# DiveComputer_Flash.net
KiCad netlist of a schematic drawn in EAGLE
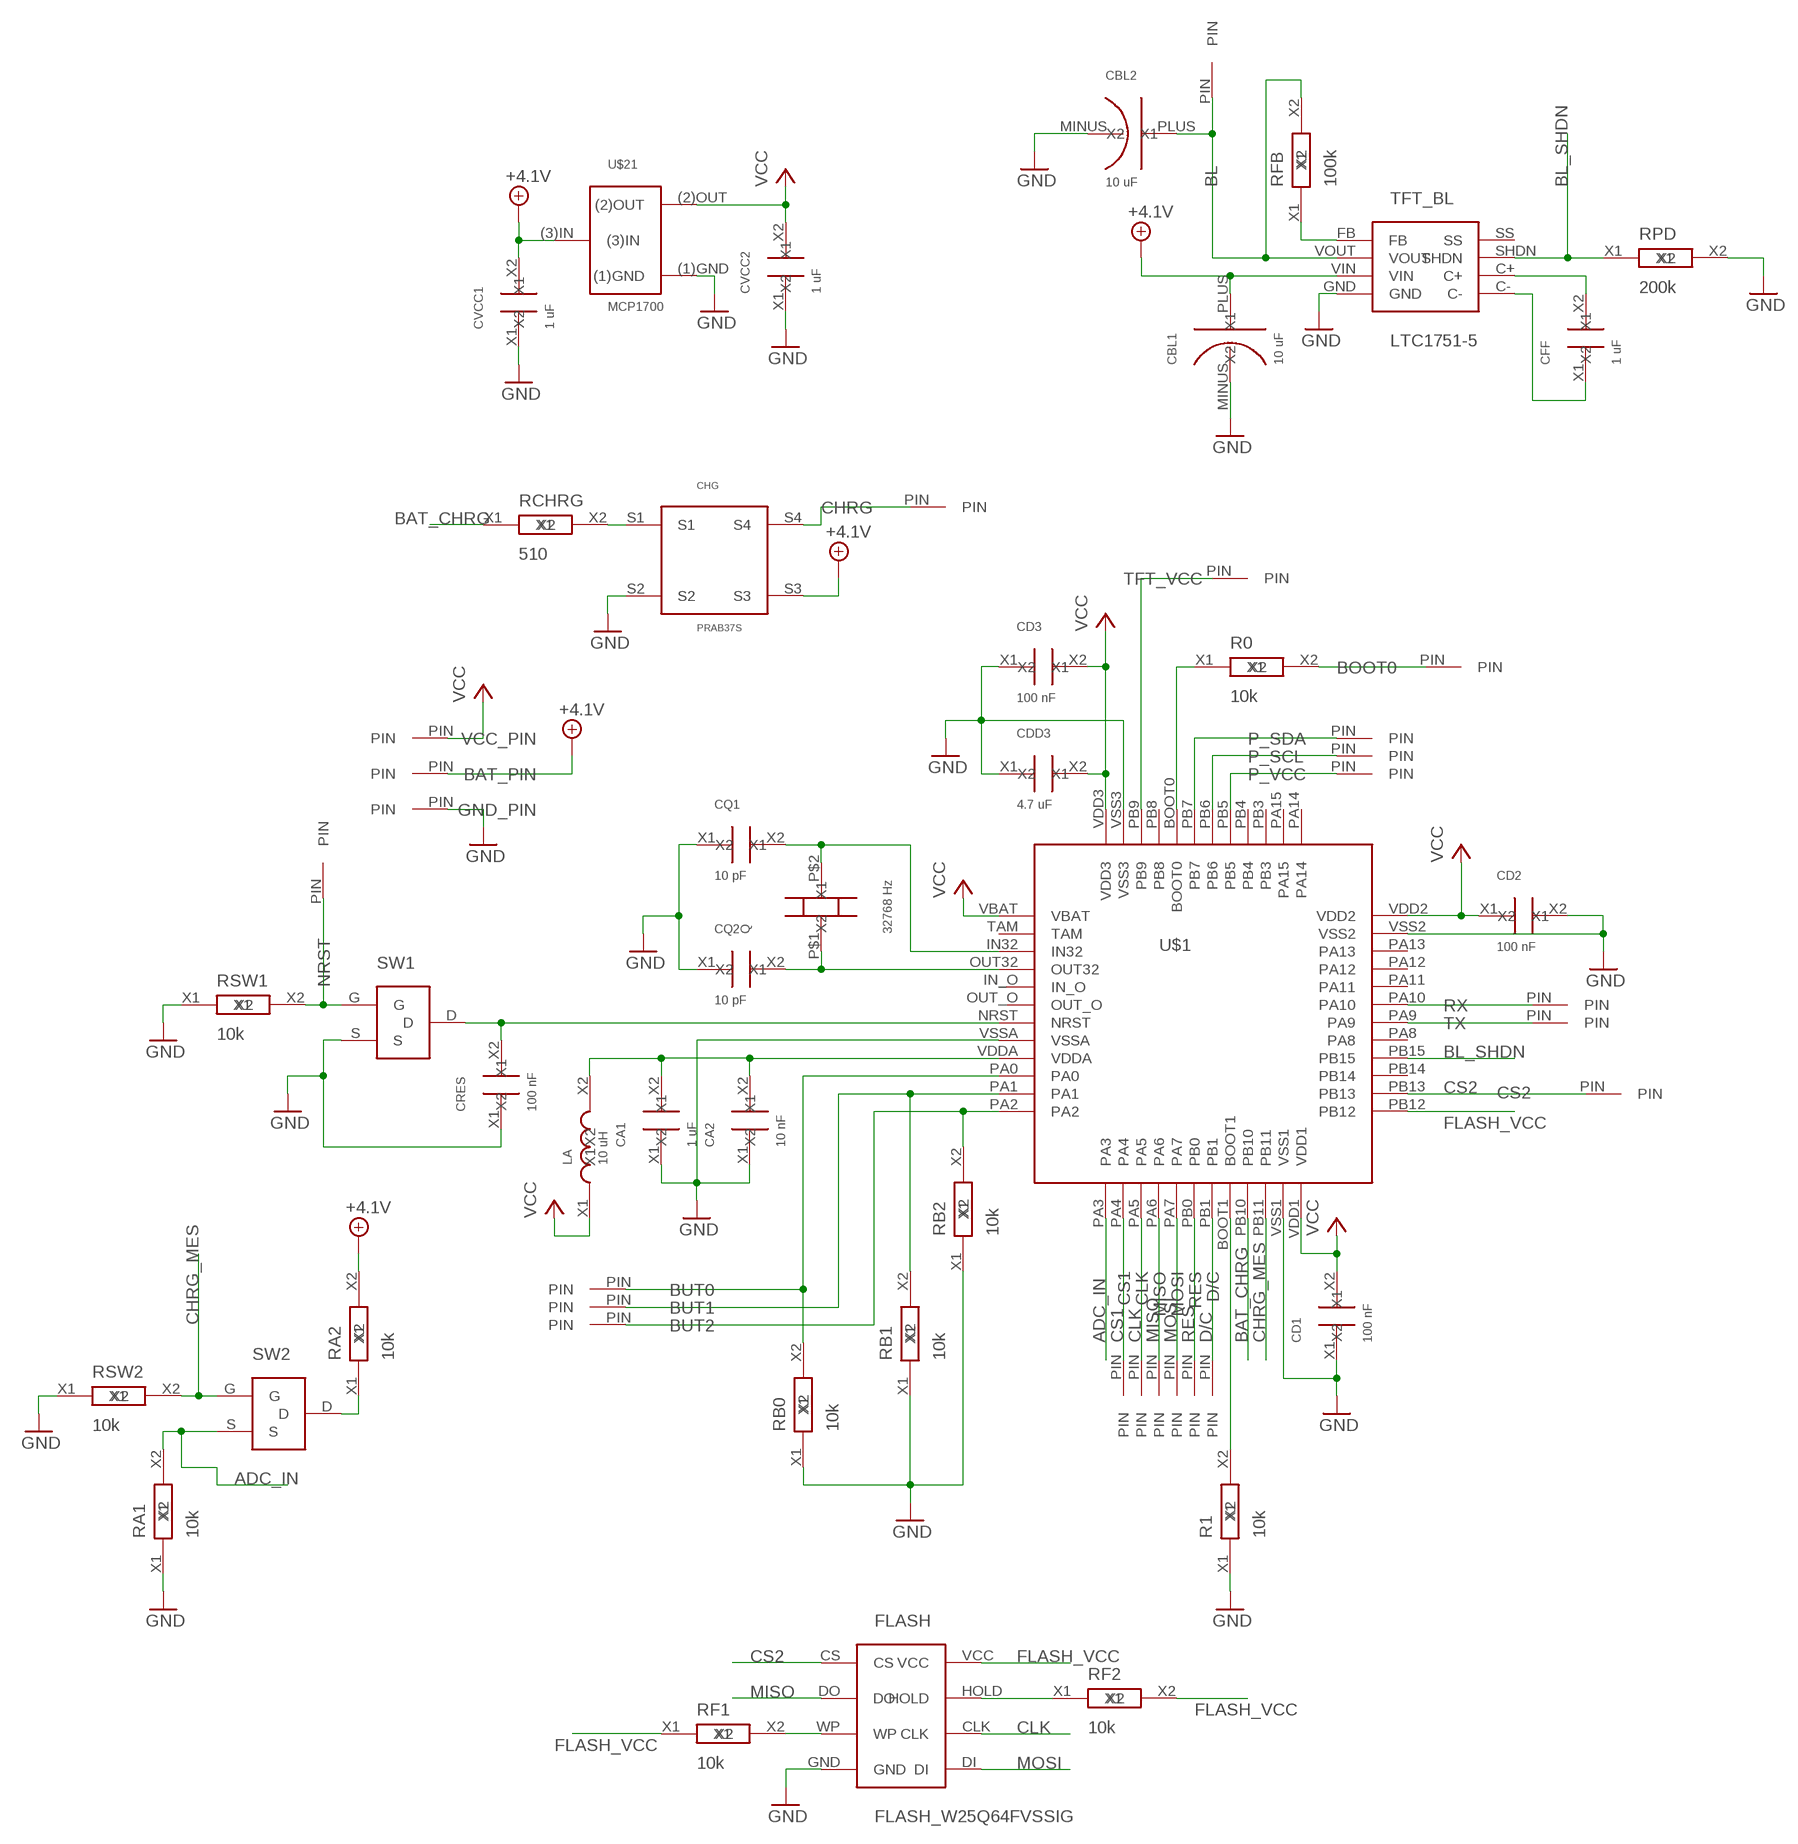
[diagram p0: schematic, sheet 1]

(export (version "E")
  (design (tool "Eeschema 10.0.6"))
  (components
    (comp (ref "BAT_PIN")
      (value "PIN_06")
      (footprint "eagle-import:PIN_06")
      (libsource (lib "eagle-import") (part "PIN_06"))
    )
    (comp (ref "BL")
      (value "PIN_06")
      (footprint "eagle-import:PIN_06")
      (libsource (lib "eagle-import") (part "PIN_06"))
    )
    (comp (ref "BOOT0")
      (value "PIN_06")
      (footprint "eagle-import:PIN_06")
      (libsource (lib "eagle-import") (part "PIN_06"))
    )
    (comp (ref "BUT0")
      (value "PIN_06")
      (footprint "eagle-import:PIN_06")
      (libsource (lib "eagle-import") (part "PIN_06"))
    )
    (comp (ref "BUT1")
      (value "PIN_06")
      (footprint "eagle-import:PIN_06")
      (libsource (lib "eagle-import") (part "PIN_06"))
    )
    (comp (ref "BUT2")
      (value "PIN_06")
      (footprint "eagle-import:PIN_06")
      (libsource (lib "eagle-import") (part "PIN_06"))
    )
    (comp (ref "CA1")
      (value "1 uF")
      (footprint "eagle-import:SMD_2.1X1.25")
      (libsource (lib "eagle-import") (part "C_SMD_2.1X1.25"))
    )
    (comp (ref "CA2")
      (value "10 nF")
      (footprint "eagle-import:SMD_2.1X1.25")
      (libsource (lib "eagle-import") (part "C_SMD_2.1X1.25"))
    )
    (comp (ref "CBL1")
      (value "10 uF")
      (footprint "eagle-import:C_SMD_TA_A")
      (libsource (lib "eagle-import") (part "C_SMD_TA_A"))
    )
    (comp (ref "CBL2")
      (value "10 uF")
      (footprint "eagle-import:C_SMD_TA_A")
      (libsource (lib "eagle-import") (part "C_SMD_TA_A"))
    )
    (comp (ref "CD1")
      (value "100 nF")
      (footprint "eagle-import:SMD_2.1X1.25")
      (libsource (lib "eagle-import") (part "C_SMD_2.1X1.25"))
    )
    (comp (ref "CD2")
      (value "100 nF")
      (footprint "eagle-import:SMD_2.1X1.25")
      (libsource (lib "eagle-import") (part "C_SMD_2.1X1.25"))
    )
    (comp (ref "CD3")
      (value "100 nF")
      (footprint "eagle-import:SMD_2.1X1.25")
      (libsource (lib "eagle-import") (part "C_SMD_2.1X1.25"))
    )
    (comp (ref "CDD3")
      (value "4.7 uF")
      (footprint "eagle-import:SMD_2.1X1.25")
      (libsource (lib "eagle-import") (part "C_SMD_2.1X1.25"))
    )
    (comp (ref "CFF")
      (value "1 uF")
      (footprint "eagle-import:SMD_2.1X1.25")
      (libsource (lib "eagle-import") (part "C_SMD_2.1X1.25"))
    )
    (comp (ref "CHG")
      (value "PRAB37S")
      (footprint "eagle-import:PRAB37S")
      (libsource (lib "eagle-import") (part "PRAB37S"))
    )
    (comp (ref "CHRG")
      (value "PIN_06")
      (footprint "eagle-import:PIN_06")
      (libsource (lib "eagle-import") (part "PIN_06"))
    )
    (comp (ref "CLK")
      (value "PIN_06")
      (footprint "eagle-import:PIN_06")
      (libsource (lib "eagle-import") (part "PIN_06"))
    )
    (comp (ref "CQ1")
      (value "10 pF")
      (footprint "eagle-import:SMD_2.1X1.25")
      (libsource (lib "eagle-import") (part "C_SMD_2.1X1.25"))
    )
    (comp (ref "CQ2")
      (value "10 pF")
      (footprint "eagle-import:SMD_2.1X1.25")
      (libsource (lib "eagle-import") (part "C_SMD_2.1X1.25"))
    )
    (comp (ref "CRES")
      (value "100 nF")
      (footprint "eagle-import:SMD_2.1X1.25")
      (libsource (lib "eagle-import") (part "C_SMD_2.1X1.25"))
    )
    (comp (ref "CS1")
      (value "PIN_06")
      (footprint "eagle-import:PIN_06")
      (libsource (lib "eagle-import") (part "PIN_06"))
    )
    (comp (ref "CS2")
      (value "PIN_06")
      (footprint "eagle-import:PIN_06")
      (libsource (lib "eagle-import") (part "PIN_06"))
    )
    (comp (ref "CVCC1")
      (value "1 uF")
      (footprint "eagle-import:SMD_2.1X1.25")
      (libsource (lib "eagle-import") (part "C_SMD_2.1X1.25"))
    )
    (comp (ref "CVCC2")
      (value "1 uF")
      (footprint "eagle-import:SMD_2.1X1.25")
      (libsource (lib "eagle-import") (part "C_SMD_2.1X1.25"))
    )
    (comp (ref "D/C")
      (value "PIN_06")
      (footprint "eagle-import:PIN_06")
      (libsource (lib "eagle-import") (part "PIN_06"))
    )
    (comp (ref "FLASH")
      (value "FLASH_W25Q64FVSSIG")
      (footprint "eagle-import:FLASH_W25Q64FVSSIG")
      (libsource (lib "eagle-import") (part "FLASH_W25Q64FVSSIG"))
    )
    (comp (ref "GND_PIN")
      (value "PIN_06")
      (footprint "eagle-import:PIN_06")
      (libsource (lib "eagle-import") (part "PIN_06"))
    )
    (comp (ref "LA")
      (value "10 uH")
      (footprint "eagle-import:SMD_2.1X1.25")
      (libsource (lib "eagle-import") (part "L_SMD_2.1X1.25"))
    )
    (comp (ref "MISO")
      (value "PIN_06")
      (footprint "eagle-import:PIN_06")
      (libsource (lib "eagle-import") (part "PIN_06"))
    )
    (comp (ref "MOSI")
      (value "PIN_06")
      (footprint "eagle-import:PIN_06")
      (libsource (lib "eagle-import") (part "PIN_06"))
    )
    (comp (ref "NRST")
      (value "PIN_06")
      (footprint "eagle-import:PIN_06")
      (libsource (lib "eagle-import") (part "PIN_06"))
    )
    (comp (ref "P_SCL")
      (value "PIN_06")
      (footprint "eagle-import:PIN_06")
      (libsource (lib "eagle-import") (part "PIN_06"))
    )
    (comp (ref "P_SDA")
      (value "PIN_06")
      (footprint "eagle-import:PIN_06")
      (libsource (lib "eagle-import") (part "PIN_06"))
    )
    (comp (ref "P_VCC")
      (value "PIN_06")
      (footprint "eagle-import:PIN_06")
      (libsource (lib "eagle-import") (part "PIN_06"))
    )
    (comp (ref "Q")
      (value "32768 Hz")
      (footprint "eagle-import:QUARTZ_CYL")
      (libsource (lib "eagle-import") (part "QUARTZ_CYL"))
    )
    (comp (ref "R0")
      (value "10k")
      (footprint "eagle-import:SMD_2.1X1.25")
      (libsource (lib "eagle-import") (part "R_SMD_2.1X1.25"))
    )
    (comp (ref "R1")
      (value "10k")
      (footprint "eagle-import:SMD_2.1X1.25")
      (libsource (lib "eagle-import") (part "R_SMD_2.1X1.25"))
    )
    (comp (ref "RA1")
      (value "10k")
      (footprint "eagle-import:SMD_2.1X1.25")
      (libsource (lib "eagle-import") (part "R_SMD_2.1X1.25"))
    )
    (comp (ref "RA2")
      (value "10k")
      (footprint "eagle-import:SMD_2.1X1.25")
      (libsource (lib "eagle-import") (part "R_SMD_2.1X1.25"))
    )
    (comp (ref "RB0")
      (value "10k")
      (footprint "eagle-import:SMD_2.1X1.25")
      (libsource (lib "eagle-import") (part "R_SMD_2.1X1.25"))
    )
    (comp (ref "RB1")
      (value "10k")
      (footprint "eagle-import:SMD_2.1X1.25")
      (libsource (lib "eagle-import") (part "R_SMD_2.1X1.25"))
    )
    (comp (ref "RB2")
      (value "10k")
      (footprint "eagle-import:SMD_2.1X1.25")
      (libsource (lib "eagle-import") (part "R_SMD_2.1X1.25"))
    )
    (comp (ref "RCHRG")
      (value "510")
      (footprint "eagle-import:SMD_2.1X1.25")
      (libsource (lib "eagle-import") (part "R_SMD_2.1X1.25"))
    )
    (comp (ref "RES")
      (value "PIN_06")
      (footprint "eagle-import:PIN_06")
      (libsource (lib "eagle-import") (part "PIN_06"))
    )
    (comp (ref "RF1")
      (value "10k")
      (footprint "eagle-import:SMD_2.1X1.25")
      (libsource (lib "eagle-import") (part "R_SMD_2.1X1.25"))
    )
    (comp (ref "RF2")
      (value "10k")
      (footprint "eagle-import:SMD_2.1X1.25")
      (libsource (lib "eagle-import") (part "R_SMD_2.1X1.25"))
    )
    (comp (ref "RFB")
      (value "100k")
      (footprint "eagle-import:SMD_2.1X1.25")
      (libsource (lib "eagle-import") (part "R_SMD_2.1X1.25"))
    )
    (comp (ref "RPD")
      (value "200k")
      (footprint "eagle-import:SMD_2.1X1.25")
      (libsource (lib "eagle-import") (part "R_SMD_2.1X1.25"))
    )
    (comp (ref "RSW1")
      (value "10k")
      (footprint "eagle-import:SMD_2.1X1.25")
      (libsource (lib "eagle-import") (part "R_SMD_2.1X1.25"))
    )
    (comp (ref "RSW2")
      (value "10k")
      (footprint "eagle-import:SMD_2.1X1.25")
      (libsource (lib "eagle-import") (part "R_SMD_2.1X1.25"))
    )
    (comp (ref "RX")
      (value "PIN_06")
      (footprint "eagle-import:PIN_06")
      (libsource (lib "eagle-import") (part "PIN_06"))
    )
    (comp (ref "SW1")
      (value "IRFML8244TRPBF")
      (footprint "eagle-import:IRFML8244TRPBF")
      (libsource (lib "eagle-import") (part "IRFML8244TRPBF"))
    )
    (comp (ref "SW2")
      (value "IRFML8244TRPBF")
      (footprint "eagle-import:IRFML8244TRPBF")
      (libsource (lib "eagle-import") (part "IRFML8244TRPBF"))
    )
    (comp (ref "TFT_BL")
      (value "LTC1751-5")
      (footprint "eagle-import:LTC1751-5")
      (libsource (lib "eagle-import") (part "LTC1751-5"))
    )
    (comp (ref "TFT_VCC")
      (value "PIN_06")
      (footprint "eagle-import:PIN_06")
      (libsource (lib "eagle-import") (part "PIN_06"))
    )
    (comp (ref "TX")
      (value "PIN_06")
      (footprint "eagle-import:PIN_06")
      (libsource (lib "eagle-import") (part "PIN_06"))
    )
    (comp (ref "U$1")
      (value "STM32F103CBT6")
      (footprint "eagle-import:STM32F103CBT6")
      (libsource (lib "eagle-import") (part "STM32F103CBT6"))
    )
    (comp (ref "U$21")
      (value "MCP1700")
      (footprint "eagle-import:MCP1700")
      (libsource (lib "eagle-import") (part "MCP1700"))
    )
    (comp (ref "VCC_PIN")
      (value "PIN_06")
      (footprint "eagle-import:PIN_06")
      (libsource (lib "eagle-import") (part "PIN_06"))
    )
  )
  (nets
    (net (code "1") (name "+4.1V") (class "Default")
      (node (ref "BAT_PIN") (pin "PIN") (pinfunction "PIN_PIN") (pintype "bidirectional"))
      (node (ref "CBL1") (pin "PLUS") (pinfunction "X2_PLUS") (pintype "bidirectional"))
      (node (ref "CHG") (pin "S3") (pinfunction "S3_S3") (pintype "bidirectional"))
      (node (ref "CVCC1") (pin "X2") (pinfunction "X2_X2") (pintype "bidirectional"))
      (node (ref "RA2") (pin "X2") (pinfunction "X2_X2") (pintype "bidirectional"))
      (node (ref "TFT_BL") (pin "VIN") (pinfunction "VIN_VIN") (pintype "bidirectional"))
      (node (ref "U$21") (pin "(3)IN") (pinfunction "(3)IN_(3)IN") (pintype "bidirectional"))
    )
    (net (code "2") (name "/ADC_IN") (class "Default")
      (node (ref "RA1") (pin "X2") (pinfunction "X2_X2") (pintype "bidirectional"))
      (node (ref "SW2") (pin "S") (pinfunction "S_S") (pintype "bidirectional"))
      (node (ref "U$1") (pin "PA3") (pinfunction "PA3_PA3") (pintype "bidirectional"))
    )
    (net (code "3") (name "/BAT_CHRG") (class "Default")
      (node (ref "RCHRG") (pin "X1") (pinfunction "X1_X1") (pintype "bidirectional"))
      (node (ref "U$1") (pin "PB10") (pinfunction "PB10_PB10") (pintype "bidirectional"))
    )
    (net (code "4") (name "/BL_SHDN") (class "Default")
      (node (ref "RPD") (pin "X1") (pinfunction "X1_X1") (pintype "bidirectional"))
      (node (ref "TFT_BL") (pin "SHDN") (pinfunction "SHDN_SHDN") (pintype "bidirectional"))
      (node (ref "U$1") (pin "PB15") (pinfunction "PB15_PB15") (pintype "bidirectional"))
    )
    (net (code "5") (name "/CHRG_MES") (class "Default")
      (node (ref "RSW2") (pin "X2") (pinfunction "X2_X2") (pintype "bidirectional"))
      (node (ref "SW2") (pin "G") (pinfunction "G_G") (pintype "bidirectional"))
      (node (ref "U$1") (pin "PB11") (pinfunction "PB11_PB11") (pintype "bidirectional"))
    )
    (net (code "6") (name "/CLK") (class "Default")
      (node (ref "CLK") (pin "PIN") (pinfunction "PIN_PIN") (pintype "bidirectional"))
      (node (ref "FLASH") (pin "CLK") (pinfunction "CLK_CLK") (pintype "bidirectional"))
      (node (ref "U$1") (pin "PA5") (pinfunction "PA5_PA5") (pintype "bidirectional"))
    )
    (net (code "7") (name "/CS1") (class "Default")
      (node (ref "CS1") (pin "PIN") (pinfunction "PIN_PIN") (pintype "bidirectional"))
      (node (ref "U$1") (pin "PA4") (pinfunction "PA4_PA4") (pintype "bidirectional"))
    )
    (net (code "8") (name "/CS2") (class "Default")
      (node (ref "CS2") (pin "PIN") (pinfunction "PIN_PIN") (pintype "bidirectional"))
      (node (ref "FLASH") (pin "CS") (pinfunction "CS_CS") (pintype "bidirectional"))
      (node (ref "U$1") (pin "PB13") (pinfunction "PB13_PB13") (pintype "bidirectional"))
    )
    (net (code "9") (name "/D{slash}C") (class "Default")
      (node (ref "D/C") (pin "PIN") (pinfunction "PIN_PIN") (pintype "bidirectional"))
      (node (ref "U$1") (pin "PB1") (pinfunction "PB1_PB1") (pintype "bidirectional"))
    )
    (net (code "10") (name "/FLASH_VCC") (class "Default")
      (node (ref "FLASH") (pin "VCC") (pinfunction "VCC_VCC") (pintype "bidirectional"))
      (node (ref "RF1") (pin "X1") (pinfunction "X1_X1") (pintype "bidirectional"))
      (node (ref "RF2") (pin "X2") (pinfunction "X2_X2") (pintype "bidirectional"))
      (node (ref "U$1") (pin "PB12") (pinfunction "PB12_PB12") (pintype "bidirectional"))
    )
    (net (code "11") (name "/MISO") (class "Default")
      (node (ref "FLASH") (pin "DO") (pinfunction "DO_DO") (pintype "bidirectional"))
      (node (ref "MISO") (pin "PIN") (pinfunction "PIN_PIN") (pintype "bidirectional"))
      (node (ref "U$1") (pin "PA6") (pinfunction "PA6_PA6") (pintype "bidirectional"))
    )
    (net (code "12") (name "/MOSI") (class "Default")
      (node (ref "FLASH") (pin "DI") (pinfunction "DI_DI") (pintype "bidirectional"))
      (node (ref "MOSI") (pin "PIN") (pinfunction "PIN_PIN") (pintype "bidirectional"))
      (node (ref "U$1") (pin "PA7") (pinfunction "PA7_PA7") (pintype "bidirectional"))
    )
    (net (code "13") (name "/RES") (class "Default")
      (node (ref "RES") (pin "PIN") (pinfunction "PIN_PIN") (pintype "bidirectional"))
      (node (ref "U$1") (pin "PB0") (pinfunction "PB0_PB0") (pintype "bidirectional"))
    )
    (net (code "14") (name "GND") (class "Default")
      (node (ref "CA1") (pin "X1") (pinfunction "X1_X1") (pintype "bidirectional"))
      (node (ref "CA2") (pin "X1") (pinfunction "X1_X1") (pintype "bidirectional"))
      (node (ref "CBL1") (pin "MINUS") (pinfunction "X1_MINUS") (pintype "bidirectional"))
      (node (ref "CBL2") (pin "MINUS") (pinfunction "X1_MINUS") (pintype "bidirectional"))
      (node (ref "CD1") (pin "X1") (pinfunction "X1_X1") (pintype "bidirectional"))
      (node (ref "CD2") (pin "X2") (pinfunction "X2_X2") (pintype "bidirectional"))
      (node (ref "CD3") (pin "X1") (pinfunction "X1_X1") (pintype "bidirectional"))
      (node (ref "CDD3") (pin "X1") (pinfunction "X1_X1") (pintype "bidirectional"))
      (node (ref "CHG") (pin "S2") (pinfunction "S2_S2") (pintype "bidirectional"))
      (node (ref "CQ1") (pin "X1") (pinfunction "X1_X1") (pintype "bidirectional"))
      (node (ref "CQ2") (pin "X1") (pinfunction "X1_X1") (pintype "bidirectional"))
      (node (ref "CRES") (pin "X1") (pinfunction "X1_X1") (pintype "bidirectional"))
      (node (ref "CVCC1") (pin "X1") (pinfunction "X1_X1") (pintype "bidirectional"))
      (node (ref "CVCC2") (pin "X1") (pinfunction "X1_X1") (pintype "bidirectional"))
      (node (ref "FLASH") (pin "GND") (pinfunction "GND_GND") (pintype "bidirectional"))
      (node (ref "GND_PIN") (pin "PIN") (pinfunction "PIN_PIN") (pintype "bidirectional"))
      (node (ref "R1") (pin "X1") (pinfunction "X1_X1") (pintype "bidirectional"))
      (node (ref "RA1") (pin "X1") (pinfunction "X1_X1") (pintype "bidirectional"))
      (node (ref "RB0") (pin "X1") (pinfunction "X1_X1") (pintype "bidirectional"))
      (node (ref "RB1") (pin "X1") (pinfunction "X1_X1") (pintype "bidirectional"))
      (node (ref "RB2") (pin "X1") (pinfunction "X1_X1") (pintype "bidirectional"))
      (node (ref "RPD") (pin "X2") (pinfunction "X2_X2") (pintype "bidirectional"))
      (node (ref "RSW1") (pin "X1") (pinfunction "X1_X1") (pintype "bidirectional"))
      (node (ref "RSW2") (pin "X1") (pinfunction "X1_X1") (pintype "bidirectional"))
      (node (ref "SW1") (pin "S") (pinfunction "S_S") (pintype "bidirectional"))
      (node (ref "TFT_BL") (pin "GND") (pinfunction "GND_GND") (pintype "bidirectional"))
      (node (ref "U$1") (pin "VSS1") (pinfunction "VSS1_VSS1") (pintype "bidirectional"))
      (node (ref "U$1") (pin "VSS2") (pinfunction "VSS2_VSS2") (pintype "bidirectional"))
      (node (ref "U$1") (pin "VSS3") (pinfunction "VSS3_VSS3") (pintype "bidirectional"))
      (node (ref "U$1") (pin "VSSA") (pinfunction "VSSA_VSSA") (pintype "bidirectional"))
      (node (ref "U$21") (pin "(1)GND") (pinfunction "(1)GND_(1)GND") (pintype "bidirectional"))
    )
    (net (code "15") (name "Net-(BOOT0-PadPIN)") (class "Default")
      (node (ref "BOOT0") (pin "PIN") (pinfunction "PIN_PIN") (pintype "bidirectional"))
      (node (ref "R0") (pin "X2") (pinfunction "X2_X2") (pintype "bidirectional"))
    )
    (net (code "16") (name "Net-(BUT0-PadPIN)") (class "Default")
      (node (ref "BUT0") (pin "PIN") (pinfunction "PIN_PIN") (pintype "bidirectional"))
      (node (ref "RB0") (pin "X2") (pinfunction "X2_X2") (pintype "bidirectional"))
      (node (ref "U$1") (pin "PA0") (pinfunction "PA0_PA0") (pintype "bidirectional"))
    )
    (net (code "17") (name "Net-(BUT1-PadPIN)") (class "Default")
      (node (ref "BUT1") (pin "PIN") (pinfunction "PIN_PIN") (pintype "bidirectional"))
      (node (ref "RB1") (pin "X2") (pinfunction "X2_X2") (pintype "bidirectional"))
      (node (ref "U$1") (pin "PA1") (pinfunction "PA1_PA1") (pintype "bidirectional"))
    )
    (net (code "18") (name "Net-(BUT2-PadPIN)") (class "Default")
      (node (ref "BUT2") (pin "PIN") (pinfunction "PIN_PIN") (pintype "bidirectional"))
      (node (ref "RB2") (pin "X2") (pinfunction "X2_X2") (pintype "bidirectional"))
      (node (ref "U$1") (pin "PA2") (pinfunction "PA2_PA2") (pintype "bidirectional"))
    )
    (net (code "19") (name "Net-(CA1-PadX2)") (class "Default")
      (node (ref "CA1") (pin "X2") (pinfunction "X2_X2") (pintype "bidirectional"))
      (node (ref "CA2") (pin "X2") (pinfunction "X2_X2") (pintype "bidirectional"))
      (node (ref "LA") (pin "X2") (pinfunction "X2_X2") (pintype "bidirectional"))
      (node (ref "U$1") (pin "VDDA") (pinfunction "VDDA_VDDA") (pintype "bidirectional"))
    )
    (net (code "20") (name "Net-(CBL2-X2)") (class "Default")
      (node (ref "BL") (pin "PIN") (pinfunction "PIN_PIN") (pintype "bidirectional"))
      (node (ref "CBL2") (pin "PLUS") (pinfunction "X2_PLUS") (pintype "bidirectional"))
      (node (ref "RFB") (pin "X2") (pinfunction "X2_X2") (pintype "bidirectional"))
      (node (ref "TFT_BL") (pin "VOUT") (pinfunction "VOUT_VOUT") (pintype "bidirectional"))
    )
    (net (code "21") (name "Net-(CFF-PadX1)") (class "Default")
      (node (ref "CFF") (pin "X1") (pinfunction "X1_X1") (pintype "bidirectional"))
      (node (ref "TFT_BL") (pin "C-") (pinfunction "C-_C-") (pintype "bidirectional"))
    )
    (net (code "22") (name "Net-(CFF-PadX2)") (class "Default")
      (node (ref "CFF") (pin "X2") (pinfunction "X2_X2") (pintype "bidirectional"))
      (node (ref "TFT_BL") (pin "C+") (pinfunction "C+_C+") (pintype "bidirectional"))
    )
    (net (code "23") (name "Net-(CHG-PadS1)") (class "Default")
      (node (ref "CHG") (pin "S1") (pinfunction "S1_S1") (pintype "bidirectional"))
      (node (ref "RCHRG") (pin "X2") (pinfunction "X2_X2") (pintype "bidirectional"))
    )
    (net (code "24") (name "Net-(CHG-PadS4)") (class "Default")
      (node (ref "CHG") (pin "S4") (pinfunction "S4_S4") (pintype "bidirectional"))
      (node (ref "CHRG") (pin "PIN") (pinfunction "PIN_PIN") (pintype "bidirectional"))
    )
    (net (code "25") (name "Net-(CRES-PadX2)") (class "Default")
      (node (ref "CRES") (pin "X2") (pinfunction "X2_X2") (pintype "bidirectional"))
      (node (ref "SW1") (pin "D") (pinfunction "D_D") (pintype "bidirectional"))
      (node (ref "U$1") (pin "NRST") (pinfunction "NRST_NRST") (pintype "bidirectional"))
    )
    (net (code "26") (name "Net-(FLASH-PadHOLD)") (class "Default")
      (node (ref "FLASH") (pin "HOLD") (pinfunction "HOLD_HOLD") (pintype "bidirectional"))
      (node (ref "RF2") (pin "X1") (pinfunction "X1_X1") (pintype "bidirectional"))
    )
    (net (code "27") (name "Net-(FLASH-PadWP)") (class "Default")
      (node (ref "FLASH") (pin "WP") (pinfunction "WP_WP") (pintype "bidirectional"))
      (node (ref "RF1") (pin "X2") (pinfunction "X2_X2") (pintype "bidirectional"))
    )
    (net (code "28") (name "Net-(NRST-PadPIN)") (class "Default")
      (node (ref "NRST") (pin "PIN") (pinfunction "PIN_PIN") (pintype "bidirectional"))
      (node (ref "RSW1") (pin "X2") (pinfunction "X2_X2") (pintype "bidirectional"))
      (node (ref "SW1") (pin "G") (pinfunction "G_G") (pintype "bidirectional"))
    )
    (net (code "29") (name "Net-(P_SCL-PadPIN)") (class "Default")
      (node (ref "P_SCL") (pin "PIN") (pinfunction "PIN_PIN") (pintype "bidirectional"))
      (node (ref "U$1") (pin "PB6") (pinfunction "PB6_PB6") (pintype "bidirectional"))
    )
    (net (code "30") (name "Net-(P_SDA-PadPIN)") (class "Default")
      (node (ref "P_SDA") (pin "PIN") (pinfunction "PIN_PIN") (pintype "bidirectional"))
      (node (ref "U$1") (pin "PB7") (pinfunction "PB7_PB7") (pintype "bidirectional"))
    )
    (net (code "31") (name "Net-(P_VCC-PadPIN)") (class "Default")
      (node (ref "P_VCC") (pin "PIN") (pinfunction "PIN_PIN") (pintype "bidirectional"))
      (node (ref "U$1") (pin "PB5") (pinfunction "PB5_PB5") (pintype "bidirectional"))
    )
    (net (code "32") (name "Net-(Q-X1)") (class "Default")
      (node (ref "CQ2") (pin "X2") (pinfunction "X2_X2") (pintype "bidirectional"))
      (node (ref "Q") (pin "P$1") (pinfunction "X1_P$1") (pintype "bidirectional"))
      (node (ref "U$1") (pin "OUT32") (pinfunction "OUT32_OUT32") (pintype "bidirectional"))
    )
    (net (code "33") (name "Net-(Q-X2)") (class "Default")
      (node (ref "CQ1") (pin "X2") (pinfunction "X2_X2") (pintype "bidirectional"))
      (node (ref "Q") (pin "P$2") (pinfunction "X2_P$2") (pintype "bidirectional"))
      (node (ref "U$1") (pin "IN32") (pinfunction "IN32_IN32") (pintype "bidirectional"))
    )
    (net (code "34") (name "Net-(R0-PadX1)") (class "Default")
      (node (ref "R0") (pin "X1") (pinfunction "X1_X1") (pintype "bidirectional"))
      (node (ref "U$1") (pin "BOOT0") (pinfunction "BOOT0_BOOT0") (pintype "bidirectional"))
    )
    (net (code "35") (name "Net-(R1-PadX2)") (class "Default")
      (node (ref "R1") (pin "X2") (pinfunction "X2_X2") (pintype "bidirectional"))
      (node (ref "U$1") (pin "BOOT1") (pinfunction "BOOT1_BOOT1") (pintype "bidirectional"))
    )
    (net (code "36") (name "Net-(RA2-PadX1)") (class "Default")
      (node (ref "RA2") (pin "X1") (pinfunction "X1_X1") (pintype "bidirectional"))
      (node (ref "SW2") (pin "D") (pinfunction "D_D") (pintype "bidirectional"))
    )
    (net (code "37") (name "Net-(RFB-PadX1)") (class "Default")
      (node (ref "RFB") (pin "X1") (pinfunction "X1_X1") (pintype "bidirectional"))
      (node (ref "TFT_BL") (pin "FB") (pinfunction "FB_FB") (pintype "bidirectional"))
    )
    (net (code "38") (name "Net-(RX-PadPIN)") (class "Default")
      (node (ref "RX") (pin "PIN") (pinfunction "PIN_PIN") (pintype "bidirectional"))
      (node (ref "U$1") (pin "PA10") (pinfunction "PA10_PA10") (pintype "bidirectional"))
    )
    (net (code "39") (name "Net-(TFT_VCC-PadPIN)") (class "Default")
      (node (ref "TFT_VCC") (pin "PIN") (pinfunction "PIN_PIN") (pintype "bidirectional"))
      (node (ref "U$1") (pin "PB9") (pinfunction "PB9_PB9") (pintype "bidirectional"))
    )
    (net (code "40") (name "Net-(TX-PadPIN)") (class "Default")
      (node (ref "TX") (pin "PIN") (pinfunction "PIN_PIN") (pintype "bidirectional"))
      (node (ref "U$1") (pin "PA9") (pinfunction "PA9_PA9") (pintype "bidirectional"))
    )
    (net (code "41") (name "VCC") (class "Default")
      (node (ref "CD1") (pin "X2") (pinfunction "X2_X2") (pintype "bidirectional"))
      (node (ref "CD2") (pin "X1") (pinfunction "X1_X1") (pintype "bidirectional"))
      (node (ref "CD3") (pin "X2") (pinfunction "X2_X2") (pintype "bidirectional"))
      (node (ref "CDD3") (pin "X2") (pinfunction "X2_X2") (pintype "bidirectional"))
      (node (ref "CVCC2") (pin "X2") (pinfunction "X2_X2") (pintype "bidirectional"))
      (node (ref "LA") (pin "X1") (pinfunction "X1_X1") (pintype "bidirectional"))
      (node (ref "U$1") (pin "VBAT") (pinfunction "VBAT_VBAT") (pintype "bidirectional"))
      (node (ref "U$1") (pin "VDD1") (pinfunction "VDD1_VDD1") (pintype "bidirectional"))
      (node (ref "U$1") (pin "VDD2") (pinfunction "VDD2_VDD2") (pintype "bidirectional"))
      (node (ref "U$1") (pin "VDD3") (pinfunction "VDD3_VDD3") (pintype "bidirectional"))
      (node (ref "U$21") (pin "(2)OUT") (pinfunction "(2)OUT_(2)OUT") (pintype "bidirectional"))
      (node (ref "VCC_PIN") (pin "PIN") (pinfunction "PIN_PIN") (pintype "bidirectional"))
    )
    (net (code "42") (name "unconnected-(TFT_BL-PadSS)") (class "Default")
      (node (ref "TFT_BL") (pin "SS") (pinfunction "SS_SS") (pintype "bidirectional"))
    )
    (net (code "43") (name "unconnected-(U$1-PadIN_O)") (class "Default")
      (node (ref "U$1") (pin "IN_O") (pinfunction "IN_O_IN_O") (pintype "bidirectional"))
    )
    (net (code "44") (name "unconnected-(U$1-PadOUT_O)") (class "Default")
      (node (ref "U$1") (pin "OUT_O") (pinfunction "OUT_O_OUT_O") (pintype "bidirectional"))
    )
    (net (code "45") (name "unconnected-(U$1-PadPA8)") (class "Default")
      (node (ref "U$1") (pin "PA8") (pinfunction "PA8_PA8") (pintype "bidirectional"))
    )
    (net (code "46") (name "unconnected-(U$1-PadPA11)") (class "Default")
      (node (ref "U$1") (pin "PA11") (pinfunction "PA11_PA11") (pintype "bidirectional"))
    )
    (net (code "47") (name "unconnected-(U$1-PadPA12)") (class "Default")
      (node (ref "U$1") (pin "PA12") (pinfunction "PA12_PA12") (pintype "bidirectional"))
    )
    (net (code "48") (name "unconnected-(U$1-PadPA13)") (class "Default")
      (node (ref "U$1") (pin "PA13") (pinfunction "PA13_PA13") (pintype "bidirectional"))
    )
    (net (code "49") (name "unconnected-(U$1-PadPA14)") (class "Default")
      (node (ref "U$1") (pin "PA14") (pinfunction "PA14_PA14") (pintype "bidirectional"))
    )
    (net (code "50") (name "unconnected-(U$1-PadPA15)") (class "Default")
      (node (ref "U$1") (pin "PA15") (pinfunction "PA15_PA15") (pintype "bidirectional"))
    )
    (net (code "51") (name "unconnected-(U$1-PadPB3)") (class "Default")
      (node (ref "U$1") (pin "PB3") (pinfunction "PB3_PB3") (pintype "bidirectional"))
    )
    (net (code "52") (name "unconnected-(U$1-PadPB4)") (class "Default")
      (node (ref "U$1") (pin "PB4") (pinfunction "PB4_PB4") (pintype "bidirectional"))
    )
    (net (code "53") (name "unconnected-(U$1-PadPB8)") (class "Default")
      (node (ref "U$1") (pin "PB8") (pinfunction "PB8_PB8") (pintype "bidirectional"))
    )
    (net (code "54") (name "unconnected-(U$1-PadPB14)") (class "Default")
      (node (ref "U$1") (pin "PB14") (pinfunction "PB14_PB14") (pintype "bidirectional"))
    )
    (net (code "55") (name "unconnected-(U$1-PadTAM)") (class "Default")
      (node (ref "U$1") (pin "TAM") (pinfunction "TAM_TAM") (pintype "bidirectional"))
    )
  )
)
